# nano2.net
KiCad netlist of a schematic drawn in EAGLE
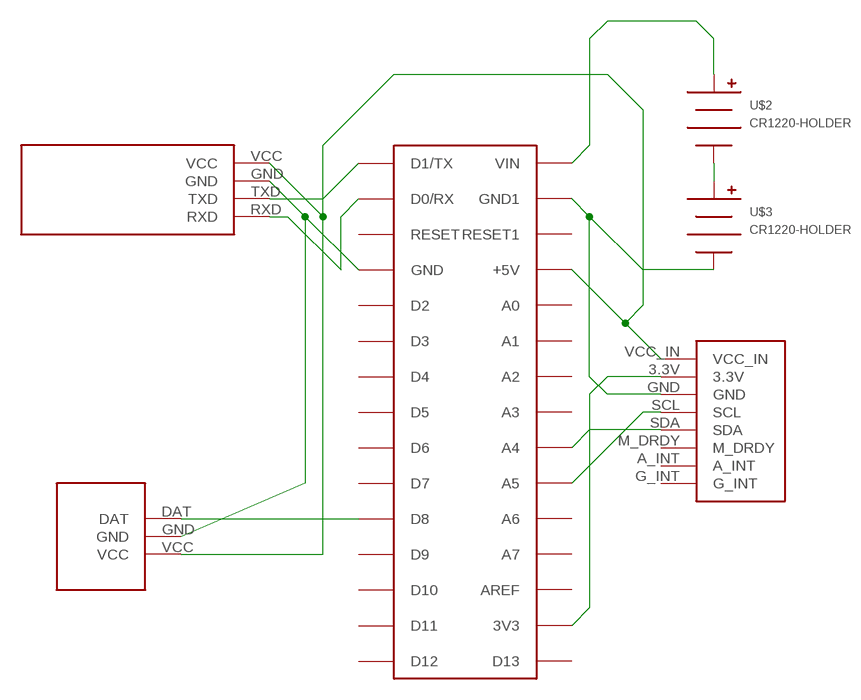
[diagram p0: schematic, sheet 1]

(export (version "E")
  (design (tool "Eeschema 10.0.6"))
  (components
    (comp (ref "U$1")
      (value "ARDUINONANO")
      (footprint "eagle-import:PDIP-32")
      (libsource (lib "eagle-import") (part "ARDUINONANO"))
    )
    (comp (ref "U$2")
      (value "CR1220-HOLDER")
      (footprint "eagle-import:HARWIN-CR1220")
      (libsource (lib "eagle-import") (part "CR1220-HOLDER"))
    )
    (comp (ref "U$3")
      (value "CR1220-HOLDER")
      (footprint "eagle-import:HARWIN-CR1220")
      (libsource (lib "eagle-import") (part "CR1220-HOLDER"))
    )
    (comp (ref "U$4")
      (value "GY85")
      (footprint "eagle-import:GY85")
      (libsource (lib "eagle-import") (part "GY85"))
    )
    (comp (ref "U$5")
      (value "HC06")
      (footprint "eagle-import:HC06")
      (libsource (lib "eagle-import") (part "HC06"))
    )
    (comp (ref "U$6")
      (value "KEY_SMALL")
      (footprint "eagle-import:KEY_SMALL")
      (libsource (lib "eagle-import") (part "KEY_SMALL"))
    )
  )
  (nets
    (net (code "1") (name "Net-(U$1-Pad+5V)") (class "Default")
      (node (ref "U$1") (pin "+5V") (pinfunction "+5V_+5V") (pintype "bidirectional"))
      (node (ref "U$4") (pin "VCC_IN") (pinfunction "VCC_IN_VCC_IN") (pintype "bidirectional"))
      (node (ref "U$5") (pin "VCC") (pinfunction "VCC_VCC") (pintype "bidirectional"))
      (node (ref "U$6") (pin "VCC") (pinfunction "VCC_VCC") (pintype "bidirectional"))
    )
    (net (code "2") (name "Net-(U$1-Pad3V3)") (class "Default")
      (node (ref "U$1") (pin "3V3") (pinfunction "3V3_3V3") (pintype "bidirectional"))
      (node (ref "U$4") (pin "3.3V") (pinfunction "3.3V_3.3V") (pintype "bidirectional"))
    )
    (net (code "3") (name "Net-(U$1-PadA4)") (class "Default")
      (node (ref "U$1") (pin "A4") (pinfunction "A4_A4") (pintype "bidirectional"))
      (node (ref "U$4") (pin "SDA") (pinfunction "SDA_SDA") (pintype "bidirectional"))
    )
    (net (code "4") (name "Net-(U$1-PadA5)") (class "Default")
      (node (ref "U$1") (pin "A5") (pinfunction "A5_A5") (pintype "bidirectional"))
      (node (ref "U$4") (pin "SCL") (pinfunction "SCL_SCL") (pintype "bidirectional"))
    )
    (net (code "5") (name "Net-(U$1-PadD0{slash}RX)") (class "Default")
      (node (ref "U$1") (pin "D0/RX") (pinfunction "D0/RX_D0/RX") (pintype "bidirectional"))
      (node (ref "U$5") (pin "RXD") (pinfunction "RXD_RXD") (pintype "bidirectional"))
    )
    (net (code "6") (name "Net-(U$1-PadD1{slash}TX)") (class "Default")
      (node (ref "U$1") (pin "D1/TX") (pinfunction "D1/TX_D1/TX") (pintype "bidirectional"))
      (node (ref "U$5") (pin "TXD") (pinfunction "TXD_TXD") (pintype "bidirectional"))
    )
    (net (code "7") (name "Net-(U$1-PadD8)") (class "Default")
      (node (ref "U$1") (pin "D8") (pinfunction "D8_D8") (pintype "bidirectional"))
      (node (ref "U$6") (pin "DAT") (pinfunction "DAT_DAT") (pintype "bidirectional"))
    )
    (net (code "8") (name "Net-(U$1-PadGND)") (class "Default")
      (node (ref "U$1") (pin "GND") (pinfunction "GND_GND") (pintype "bidirectional"))
      (node (ref "U$5") (pin "GND") (pinfunction "GND_GND") (pintype "bidirectional"))
      (node (ref "U$6") (pin "GND") (pinfunction "GND_GND") (pintype "bidirectional"))
    )
    (net (code "9") (name "Net-(U$1-PadGND1)") (class "Default")
      (node (ref "U$1") (pin "GND1") (pinfunction "GND1_GND1") (pintype "bidirectional"))
      (node (ref "U$3") (pin "NEG") (pinfunction "NEG_NEG") (pintype "bidirectional"))
      (node (ref "U$4") (pin "GND") (pinfunction "GND_GND") (pintype "bidirectional"))
    )
    (net (code "10") (name "Net-(U$1-PadVIN)") (class "Default")
      (node (ref "U$1") (pin "VIN") (pinfunction "VIN_VIN") (pintype "bidirectional"))
      (node (ref "U$2") (pin "POS") (pinfunction "POS_POS") (pintype "bidirectional"))
    )
    (net (code "11") (name "Net-(U$2-PadNEG)") (class "Default")
      (node (ref "U$2") (pin "NEG") (pinfunction "NEG_NEG") (pintype "bidirectional"))
      (node (ref "U$3") (pin "POS") (pinfunction "POS_POS") (pintype "bidirectional"))
    )
    (net (code "12") (name "unconnected-(U$1-PadA0)") (class "Default")
      (node (ref "U$1") (pin "A0") (pinfunction "A0_A0") (pintype "bidirectional"))
    )
    (net (code "13") (name "unconnected-(U$1-PadA1)") (class "Default")
      (node (ref "U$1") (pin "A1") (pinfunction "A1_A1") (pintype "bidirectional"))
    )
    (net (code "14") (name "unconnected-(U$1-PadA2)") (class "Default")
      (node (ref "U$1") (pin "A2") (pinfunction "A2_A2") (pintype "bidirectional"))
    )
    (net (code "15") (name "unconnected-(U$1-PadA3)") (class "Default")
      (node (ref "U$1") (pin "A3") (pinfunction "A3_A3") (pintype "bidirectional"))
    )
    (net (code "16") (name "unconnected-(U$1-PadA6)") (class "Default")
      (node (ref "U$1") (pin "A6") (pinfunction "A6_A6") (pintype "bidirectional"))
    )
    (net (code "17") (name "unconnected-(U$1-PadA7)") (class "Default")
      (node (ref "U$1") (pin "A7") (pinfunction "A7_A7") (pintype "bidirectional"))
    )
    (net (code "18") (name "unconnected-(U$1-PadAREF)") (class "Default")
      (node (ref "U$1") (pin "AREF") (pinfunction "AREF_AREF") (pintype "bidirectional"))
    )
    (net (code "19") (name "unconnected-(U$1-PadD2)") (class "Default")
      (node (ref "U$1") (pin "D2") (pinfunction "D2_D2") (pintype "bidirectional"))
    )
    (net (code "20") (name "unconnected-(U$1-PadD3)") (class "Default")
      (node (ref "U$1") (pin "D3") (pinfunction "D3_D3") (pintype "bidirectional"))
    )
    (net (code "21") (name "unconnected-(U$1-PadD4)") (class "Default")
      (node (ref "U$1") (pin "D4") (pinfunction "D4_D4") (pintype "bidirectional"))
    )
    (net (code "22") (name "unconnected-(U$1-PadD5)") (class "Default")
      (node (ref "U$1") (pin "D5") (pinfunction "D5_D5") (pintype "bidirectional"))
    )
    (net (code "23") (name "unconnected-(U$1-PadD6)") (class "Default")
      (node (ref "U$1") (pin "D6") (pinfunction "D6_D6") (pintype "bidirectional"))
    )
    (net (code "24") (name "unconnected-(U$1-PadD7)") (class "Default")
      (node (ref "U$1") (pin "D7") (pinfunction "D7_D7") (pintype "bidirectional"))
    )
    (net (code "25") (name "unconnected-(U$1-PadD9)") (class "Default")
      (node (ref "U$1") (pin "D9") (pinfunction "D9_D9") (pintype "bidirectional"))
    )
    (net (code "26") (name "unconnected-(U$1-PadD10)") (class "Default")
      (node (ref "U$1") (pin "D10") (pinfunction "D10_D10") (pintype "bidirectional"))
    )
    (net (code "27") (name "unconnected-(U$1-PadD11)") (class "Default")
      (node (ref "U$1") (pin "D11") (pinfunction "D11_D11") (pintype "bidirectional"))
    )
    (net (code "28") (name "unconnected-(U$1-PadD12)") (class "Default")
      (node (ref "U$1") (pin "D12") (pinfunction "D12_D12") (pintype "bidirectional"))
    )
    (net (code "29") (name "unconnected-(U$1-PadD13)") (class "Default")
      (node (ref "U$1") (pin "D13") (pinfunction "D13_D13") (pintype "bidirectional"))
    )
    (net (code "30") (name "unconnected-(U$1-PadRESET)") (class "Default")
      (node (ref "U$1") (pin "RESET") (pinfunction "RESET_RESET") (pintype "bidirectional"))
    )
    (net (code "31") (name "unconnected-(U$1-PadRESET1)") (class "Default")
      (node (ref "U$1") (pin "RESET1") (pinfunction "RESET1_RESET1") (pintype "bidirectional"))
    )
    (net (code "32") (name "unconnected-(U$4-PadA_INT)") (class "Default")
      (node (ref "U$4") (pin "A_INT") (pinfunction "A_INT_A_INT") (pintype "bidirectional"))
    )
    (net (code "33") (name "unconnected-(U$4-PadG_INT)") (class "Default")
      (node (ref "U$4") (pin "G_INT") (pinfunction "G_INT_G_INT") (pintype "bidirectional"))
    )
    (net (code "34") (name "unconnected-(U$4-PadM_DRDY)") (class "Default")
      (node (ref "U$4") (pin "M_DRDY") (pinfunction "M_DRDY_M_DRDY") (pintype "bidirectional"))
    )
  )
)
